# MCU.net
KiCad netlist of a schematic drawn in Altium Designer
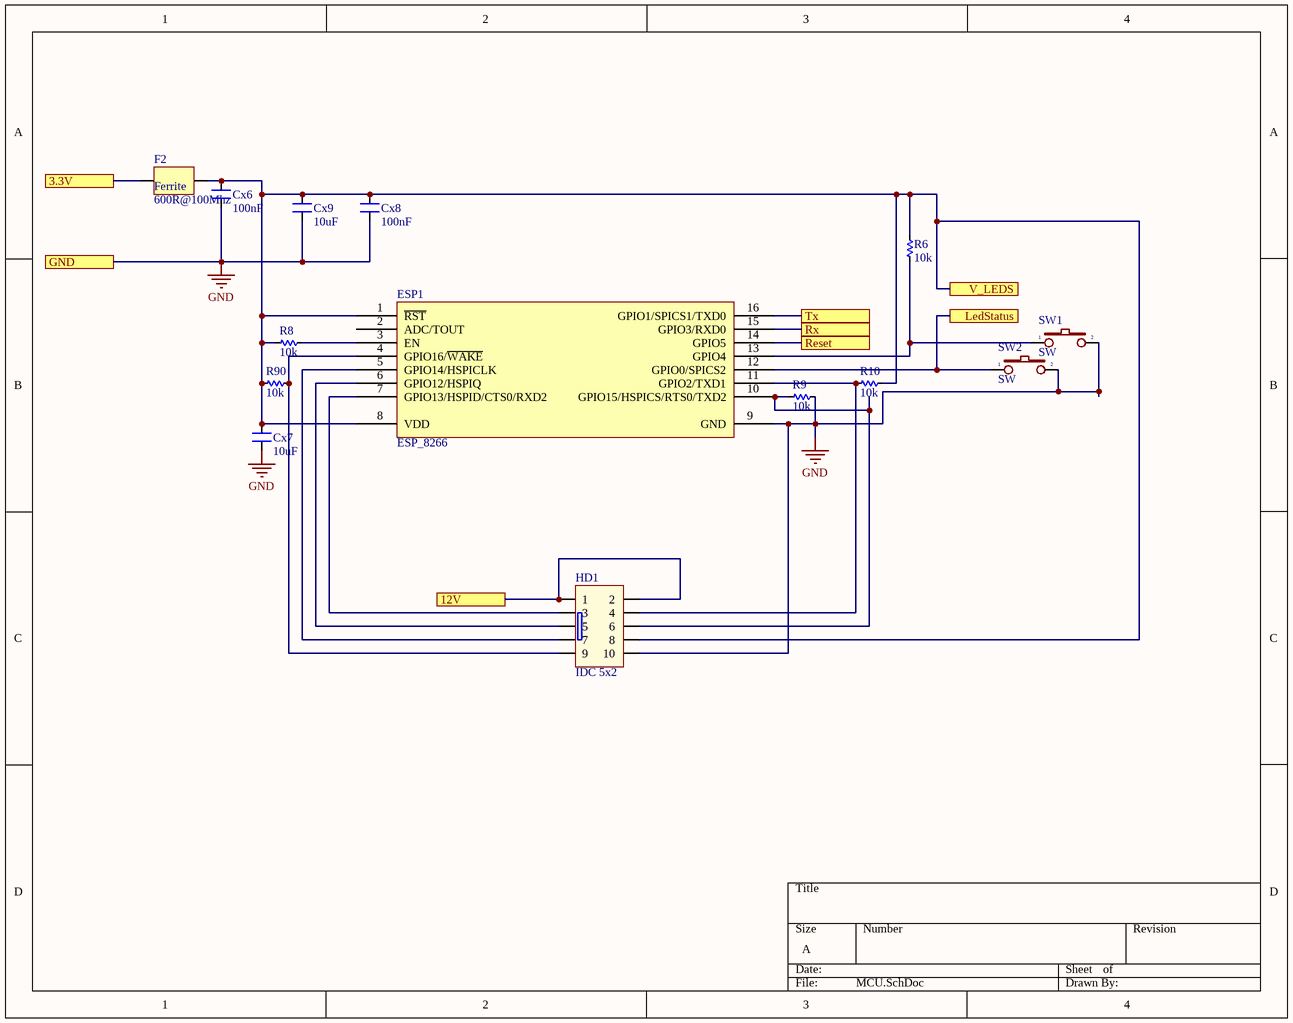
[diagram p0: MCU.SchDoc]

(export (version "E")
  (design (tool "Eeschema 10.0.6"))
  (components
    (comp (ref "Cx6") (value "100nF") (footprint "CN-SMD-0805") (libsource (lib "LIBRARY") (part "CN")))
    (comp (ref "Cx7") (value "10uF") (footprint "CN-SMD-0805") (libsource (lib "LIBRARY") (part "CN")))
    (comp (ref "Cx8") (value "100nF") (footprint "CN-SMD-0805") (libsource (lib "LIBRARY") (part "CN")))
    (comp (ref "Cx9") (value "10uF") (footprint "CN-SMD-0805") (libsource (lib "LIBRARY") (part "CN")))
    (comp (ref "ESP1")
      (value "ESP_8266")
      (footprint "ESP12_small")
      (libsource (lib "nhan") (part "ESP_8266"))
    )
    (comp (ref "F2")
      (value "600R@100Mhz")
      (footprint "Capacitor_805")
      (libsource (lib "nhan") (part "Ferrite"))
    )
    (comp (ref "HD1")
      (value "IDC 5x2")
      (footprint "IDC10-BH")
      (libsource (lib "BanLinhKien") (part "IDC 5X2"))
    )
    (comp (ref "R6")
      (value "10k")
      (footprint "RES-SMD-0805")
      (description "Resistor")
      (fields
        (field (name "MANUFACTURER") "Generic Components")
        (field (name "PUBLISHER") "Altium Hobart Technology Centre")
      )
      (libsource (lib "LIBRARY") (part "Res-SMD"))
    )
    (comp (ref "R8")
      (value "10k")
      (footprint "RES-SMD-0805")
      (description "Resistor")
      (fields
        (field (name "MANUFACTURER") "Generic Components")
        (field (name "PUBLISHER") "Altium Hobart Technology Centre")
      )
      (libsource (lib "LIBRARY") (part "Res-SMD"))
    )
    (comp (ref "R9")
      (value "10k")
      (footprint "RES-SMD-0805")
      (description "Resistor")
      (fields
        (field (name "MANUFACTURER") "Generic Components")
        (field (name "PUBLISHER") "Altium Hobart Technology Centre")
      )
      (libsource (lib "LIBRARY") (part "Res-SMD"))
    )
    (comp (ref "R10")
      (value "10k")
      (footprint "RES-SMD-0805")
      (description "Resistor")
      (fields
        (field (name "MANUFACTURER") "Generic Components")
        (field (name "PUBLISHER") "Altium Hobart Technology Centre")
      )
      (libsource (lib "LIBRARY") (part "Res-SMD"))
    )
    (comp (ref "R90")
      (value "10k")
      (footprint "RES-SMD-0805")
      (description "Resistor")
      (fields
        (field (name "MANUFACTURER") "Generic Components")
        (field (name "PUBLISHER") "Altium Hobart Technology Centre")
      )
      (libsource (lib "LIBRARY") (part "Res-SMD"))
    )
    (comp (ref "SW1")
      (value "SW")
      (footprint "SW1-DIP")
      (description "Switch button 2 pin")
      (libsource (lib "LIBRARY") (part "SW2"))
    )
    (comp (ref "SW2")
      (value "SW")
      (footprint "SW1-SMD")
      (description "Switch button 2 pin")
      (libsource (lib "LIBRARY") (part "SW2"))
    )
  )
  (nets
    (net (code "1") (name "/3.3V") (class "Default")
      (node (ref "F2") (pin "1") (pinfunction "1_1") (pintype "passive"))
    )
    (net (code "2") (name "/12V") (class "Default")
      (node (ref "HD1") (pin "1") (pinfunction "1_1") (pintype "passive"))
      (node (ref "HD1") (pin "2") (pinfunction "2_2") (pintype "passive"))
    )
    (net (code "3") (name "/LedStatus") (class "Default")
      (node (ref "ESP1") (pin "12") (pinfunction "GPIO0/SPICS2_12") (pintype "passive"))
      (node (ref "SW2") (pin "1") (pinfunction "1_1") (pintype "passive"))
    )
    (net (code "4") (name "/Reset") (class "Default")
      (node (ref "ESP1") (pin "14") (pinfunction "GPIO5_14") (pintype "passive"))
    )
    (net (code "5") (name "/Rx") (class "Default")
      (node (ref "ESP1") (pin "15") (pinfunction "GPIO3/RXD0_15") (pintype "passive"))
    )
    (net (code "6") (name "/Tx") (class "Default")
      (node (ref "ESP1") (pin "16") (pinfunction "GPIO1/SPICS1/TXD0_16") (pintype "passive"))
    )
    (net (code "7") (name "/V_LEDS") (class "Default")
      (node (ref "Cx6") (pin "2") (pinfunction "2_2") (pintype "passive"))
      (node (ref "Cx7") (pin "1") (pinfunction "1_1") (pintype "passive"))
      (node (ref "Cx8") (pin "2") (pinfunction "2_2") (pintype "passive"))
      (node (ref "Cx9") (pin "2") (pinfunction "2_2") (pintype "passive"))
      (node (ref "ESP1") (pin "1") (pinfunction "~{RST}_1") (pintype "passive"))
      (node (ref "ESP1") (pin "8") (pinfunction "VDD_8") (pintype "passive"))
      (node (ref "F2") (pin "2") (pinfunction "2_2") (pintype "passive"))
      (node (ref "HD1") (pin "8") (pinfunction "8_8") (pintype "passive"))
      (node (ref "R10") (pin "1") (pinfunction "1_1") (pintype "passive"))
      (node (ref "R6") (pin "1") (pinfunction "1_1") (pintype "passive"))
      (node (ref "R8") (pin "2") (pinfunction "2_2") (pintype "passive"))
      (node (ref "R90") (pin "2") (pinfunction "2_2") (pintype "passive"))
    )
    (net (code "8") (name "GND") (class "Default")
      (node (ref "Cx6") (pin "1") (pinfunction "1_1") (pintype "passive"))
      (node (ref "Cx7") (pin "2") (pinfunction "2_2") (pintype "passive"))
      (node (ref "Cx8") (pin "1") (pinfunction "1_1") (pintype "passive"))
      (node (ref "Cx9") (pin "1") (pinfunction "1_1") (pintype "passive"))
      (node (ref "ESP1") (pin "9") (pinfunction "GND_9") (pintype "passive"))
      (node (ref "HD1") (pin "10") (pinfunction "10_10") (pintype "passive"))
      (node (ref "R9") (pin "1") (pinfunction "1_1") (pintype "passive"))
      (node (ref "SW1") (pin "2") (pinfunction "2_2") (pintype "passive"))
      (node (ref "SW2") (pin "2") (pinfunction "2_2") (pintype "passive"))
    )
    (net (code "9") (name "Net-(ESP1-EN)") (class "Default")
      (node (ref "ESP1") (pin "3") (pinfunction "EN_3") (pintype "passive"))
      (node (ref "R8") (pin "1") (pinfunction "1_1") (pintype "passive"))
    )
    (net (code "10") (name "Net-(ESP1-GPIO2{slash}TXD1)") (class "Default")
      (node (ref "ESP1") (pin "11") (pinfunction "GPIO2/TXD1_11") (pintype "passive"))
      (node (ref "HD1") (pin "4") (pinfunction "4_4") (pintype "passive"))
      (node (ref "R10") (pin "2") (pinfunction "2_2") (pintype "passive"))
    )
    (net (code "11") (name "Net-(ESP1-GPIO4)") (class "Default")
      (node (ref "ESP1") (pin "13") (pinfunction "GPIO4_13") (pintype "passive"))
      (node (ref "R6") (pin "2") (pinfunction "2_2") (pintype "passive"))
      (node (ref "SW1") (pin "1") (pinfunction "1_1") (pintype "passive"))
    )
    (net (code "12") (name "Net-(ESP1-GPIO12{slash}HSPIQ)") (class "Default")
      (node (ref "ESP1") (pin "6") (pinfunction "GPIO12/HSPIQ_6") (pintype "passive"))
      (node (ref "HD1") (pin "5") (pinfunction "5_5") (pintype "passive"))
    )
    (net (code "13") (name "Net-(ESP1-GPIO13{slash}HSPID{slash}CTS0{slash}RXD2)") (class "Default")
      (node (ref "ESP1") (pin "7") (pinfunction "GPIO13/HSPID/CTS0/RXD2_7") (pintype "passive"))
      (node (ref "HD1") (pin "3") (pinfunction "3_3") (pintype "passive"))
    )
    (net (code "14") (name "Net-(ESP1-GPIO14{slash}HSPICLK)") (class "Default")
      (node (ref "ESP1") (pin "5") (pinfunction "GPIO14/HSPICLK_5") (pintype "passive"))
      (node (ref "HD1") (pin "7") (pinfunction "7_7") (pintype "passive"))
    )
    (net (code "15") (name "Net-(ESP1-GPIO15{slash}HSPICS{slash}RTS0{slash}TXD2)") (class "Default")
      (node (ref "ESP1") (pin "10") (pinfunction "GPIO15/HSPICS/RTS0/TXD2_10") (pintype "passive"))
      (node (ref "HD1") (pin "6") (pinfunction "6_6") (pintype "passive"))
      (node (ref "R9") (pin "2") (pinfunction "2_2") (pintype "passive"))
    )
    (net (code "16") (name "Net-(ESP1-GPIO16{slash}~{WAKE})") (class "Default")
      (node (ref "ESP1") (pin "4") (pinfunction "GPIO16/~{WAKE}_4") (pintype "passive"))
      (node (ref "HD1") (pin "9") (pinfunction "9_9") (pintype "passive"))
      (node (ref "R90") (pin "1") (pinfunction "1_1") (pintype "passive"))
    )
    (net (code "17") (name "unconnected-(ESP1-ADC{slash}TOUT-Pad2)") (class "Default")
      (node (ref "ESP1") (pin "2") (pinfunction "ADC/TOUT_2") (pintype "passive"))
    )
  )
)
